# LED_BRD.net
KiCad netlist of a schematic drawn in EAGLE
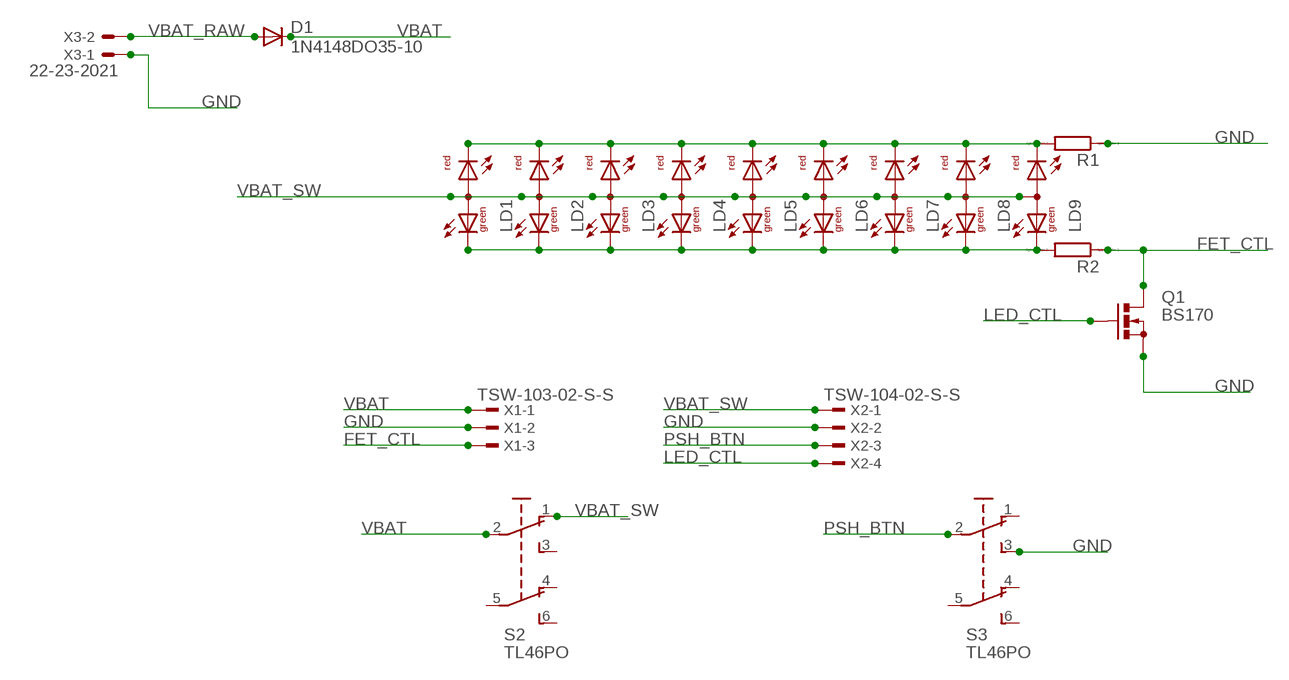
[diagram p0: schematic, sheet 1]

(export (version "E")
  (design (tool "Eeschema 10.0.6"))
  (components
    (comp (ref "D1")
      (value "1N4148DO35-10")
      (footprint "eagle-import:DO35-10")
      (libsource (lib "eagle-import") (part "1N4148DO35-10"))
    )
    (comp (ref "LD1")
      (value "DUOLED-RG-A")
      (footprint "eagle-import:DUOLED-A-5MM")
      (libsource (lib "eagle-import") (part "DUOLED-RG-A"))
    )
    (comp (ref "LD2")
      (value "DUOLED-RG-A")
      (footprint "eagle-import:DUOLED-A-5MM")
      (libsource (lib "eagle-import") (part "DUOLED-RG-A"))
    )
    (comp (ref "LD3")
      (value "DUOLED-RG-A")
      (footprint "eagle-import:DUOLED-A-5MM")
      (libsource (lib "eagle-import") (part "DUOLED-RG-A"))
    )
    (comp (ref "LD4")
      (value "DUOLED-RG-A")
      (footprint "eagle-import:DUOLED-A-5MM")
      (libsource (lib "eagle-import") (part "DUOLED-RG-A"))
    )
    (comp (ref "LD5")
      (value "DUOLED-RG-A")
      (footprint "eagle-import:DUOLED-A-5MM")
      (libsource (lib "eagle-import") (part "DUOLED-RG-A"))
    )
    (comp (ref "LD6")
      (value "DUOLED-RG-A")
      (footprint "eagle-import:DUOLED-A-5MM")
      (libsource (lib "eagle-import") (part "DUOLED-RG-A"))
    )
    (comp (ref "LD7")
      (value "DUOLED-RG-A")
      (footprint "eagle-import:DUOLED-A-5MM")
      (libsource (lib "eagle-import") (part "DUOLED-RG-A"))
    )
    (comp (ref "LD8")
      (value "DUOLED-RG-A")
      (footprint "eagle-import:DUOLED-A-5MM")
      (libsource (lib "eagle-import") (part "DUOLED-RG-A"))
    )
    (comp (ref "LD9")
      (value "DUOLED-RG-A")
      (footprint "eagle-import:DUOLED-A-5MM")
      (libsource (lib "eagle-import") (part "DUOLED-RG-A"))
    )
    (comp (ref "Q1")
      (value "BS170")
      (footprint "eagle-import:SOT54E")
      (libsource (lib "eagle-import") (part "BS170"))
    )
    (comp (ref "R1")
      (value "R0204/7")
      (footprint "eagle-import:0204_7")
      (libsource (lib "eagle-import") (part "R0204/7"))
    )
    (comp (ref "R2")
      (value "R0204/7")
      (footprint "eagle-import:0204_7")
      (libsource (lib "eagle-import") (part "R0204/7"))
    )
    (comp (ref "S2")
      (value "TL46PO")
      (footprint "eagle-import:TL4XPO")
      (libsource (lib "eagle-import") (part "TL46PO"))
    )
    (comp (ref "S3")
      (value "TL46PO")
      (footprint "eagle-import:TL4XPO")
      (libsource (lib "eagle-import") (part "TL46PO"))
    )
    (comp (ref "X1")
      (value "TSW-103-02-S-S")
      (footprint "eagle-import:TSW-103-02-S-S")
      (libsource (lib "eagle-import") (part "TSW-103-02-S-S"))
    )
    (comp (ref "X2")
      (value "TSW-104-02-S-S")
      (footprint "eagle-import:TSW-104-02-S-S")
      (libsource (lib "eagle-import") (part "TSW-104-02-S-S"))
    )
    (comp (ref "X3")
      (value "22-23-2021")
      (footprint "eagle-import:22-23-2021")
      (fields (field (name "MF") "MOLEX"))
      (libsource (lib "eagle-import") (part "22-23-2021"))
    )
  )
  (nets
    (net (code "1") (name "/FET_CTL") (class "Default")
      (node (ref "Q1") (pin "D") (pinfunction "D_D") (pintype "passive"))
      (node (ref "R2") (pin "1") (pinfunction "1_1") (pintype "passive"))
      (node (ref "X1") (pin "3") (pinfunction "1_3") (pintype "passive"))
    )
    (net (code "2") (name "/GND") (class "Default")
      (node (ref "Q1") (pin "S") (pinfunction "S_S") (pintype "passive"))
      (node (ref "R1") (pin "1") (pinfunction "1_1") (pintype "passive"))
      (node (ref "S3") (pin "3") (pinfunction "S_3") (pintype "passive"))
      (node (ref "X1") (pin "2") (pinfunction "1_2") (pintype "passive"))
      (node (ref "X2") (pin "2") (pinfunction "1_2") (pintype "passive"))
      (node (ref "X3") (pin "1") (pinfunction "S_1") (pintype "passive"))
    )
    (net (code "3") (name "/LED_CTL") (class "Default")
      (node (ref "Q1") (pin "G") (pinfunction "G_G") (pintype "passive"))
      (node (ref "X2") (pin "4") (pinfunction "1_4") (pintype "passive"))
    )
    (net (code "4") (name "/PSH_BTN") (class "Default")
      (node (ref "S3") (pin "2") (pinfunction "P_2") (pintype "passive"))
      (node (ref "X2") (pin "3") (pinfunction "1_3") (pintype "passive"))
    )
    (net (code "5") (name "/VBAT") (class "Default")
      (node (ref "D1") (pin "C") (pinfunction "C_C") (pintype "passive"))
      (node (ref "S2") (pin "2") (pinfunction "P_2") (pintype "passive"))
      (node (ref "X1") (pin "1") (pinfunction "1_1") (pintype "passive"))
    )
    (net (code "6") (name "/VBAT_RAW") (class "Default")
      (node (ref "D1") (pin "A") (pinfunction "A_A") (pintype "passive"))
      (node (ref "X3") (pin "2") (pinfunction "S_2") (pintype "passive"))
    )
    (net (code "7") (name "/VBAT_SW") (class "Default")
      (node (ref "LD1") (pin "A") (pinfunction "A_A") (pintype "passive"))
      (node (ref "LD2") (pin "A") (pinfunction "A_A") (pintype "passive"))
      (node (ref "LD3") (pin "A") (pinfunction "A_A") (pintype "passive"))
      (node (ref "LD4") (pin "A") (pinfunction "A_A") (pintype "passive"))
      (node (ref "LD5") (pin "A") (pinfunction "A_A") (pintype "passive"))
      (node (ref "LD6") (pin "A") (pinfunction "A_A") (pintype "passive"))
      (node (ref "LD7") (pin "A") (pinfunction "A_A") (pintype "passive"))
      (node (ref "LD8") (pin "A") (pinfunction "A_A") (pintype "passive"))
      (node (ref "LD9") (pin "A") (pinfunction "A_A") (pintype "passive"))
      (node (ref "S2") (pin "1") (pinfunction "O_1") (pintype "passive"))
      (node (ref "X2") (pin "1") (pinfunction "1_1") (pintype "passive"))
    )
    (net (code "8") (name "Net-(LD1-CG)") (class "Default")
      (node (ref "LD1") (pin "CX") (pinfunction "CG_CX") (pintype "passive"))
      (node (ref "LD2") (pin "CX") (pinfunction "CG_CX") (pintype "passive"))
      (node (ref "LD3") (pin "CX") (pinfunction "CG_CX") (pintype "passive"))
      (node (ref "LD4") (pin "CX") (pinfunction "CG_CX") (pintype "passive"))
      (node (ref "LD5") (pin "CX") (pinfunction "CG_CX") (pintype "passive"))
      (node (ref "LD6") (pin "CX") (pinfunction "CG_CX") (pintype "passive"))
      (node (ref "LD7") (pin "CX") (pinfunction "CG_CX") (pintype "passive"))
      (node (ref "LD8") (pin "CX") (pinfunction "CG_CX") (pintype "passive"))
      (node (ref "LD9") (pin "CX") (pinfunction "CG_CX") (pintype "passive"))
      (node (ref "R2") (pin "2") (pinfunction "2_2") (pintype "passive"))
    )
    (net (code "9") (name "Net-(LD1-PadCR)") (class "Default")
      (node (ref "LD1") (pin "CR") (pinfunction "CR_CR") (pintype "passive"))
      (node (ref "LD2") (pin "CR") (pinfunction "CR_CR") (pintype "passive"))
      (node (ref "LD3") (pin "CR") (pinfunction "CR_CR") (pintype "passive"))
      (node (ref "LD4") (pin "CR") (pinfunction "CR_CR") (pintype "passive"))
      (node (ref "LD5") (pin "CR") (pinfunction "CR_CR") (pintype "passive"))
      (node (ref "LD6") (pin "CR") (pinfunction "CR_CR") (pintype "passive"))
      (node (ref "LD7") (pin "CR") (pinfunction "CR_CR") (pintype "passive"))
      (node (ref "LD8") (pin "CR") (pinfunction "CR_CR") (pintype "passive"))
      (node (ref "LD9") (pin "CR") (pinfunction "CR_CR") (pintype "passive"))
      (node (ref "R1") (pin "2") (pinfunction "2_2") (pintype "passive"))
    )
    (net (code "10") (name "unconnected-(S2-O1-Pad4)") (class "Default")
      (node (ref "S2") (pin "4") (pinfunction "O1_4") (pintype "passive"))
    )
    (net (code "11") (name "unconnected-(S2-P1-Pad5)") (class "Default")
      (node (ref "S2") (pin "5") (pinfunction "P1_5") (pintype "passive"))
    )
    (net (code "12") (name "unconnected-(S2-S-Pad3)") (class "Default")
      (node (ref "S2") (pin "3") (pinfunction "S_3") (pintype "passive"))
    )
    (net (code "13") (name "unconnected-(S2-S1-Pad6)") (class "Default")
      (node (ref "S2") (pin "6") (pinfunction "S1_6") (pintype "passive"))
    )
    (net (code "14") (name "unconnected-(S3-O-Pad1)") (class "Default")
      (node (ref "S3") (pin "1") (pinfunction "O_1") (pintype "passive"))
    )
    (net (code "15") (name "unconnected-(S3-O1-Pad4)") (class "Default")
      (node (ref "S3") (pin "4") (pinfunction "O1_4") (pintype "passive"))
    )
    (net (code "16") (name "unconnected-(S3-P1-Pad5)") (class "Default")
      (node (ref "S3") (pin "5") (pinfunction "P1_5") (pintype "passive"))
    )
    (net (code "17") (name "unconnected-(S3-S1-Pad6)") (class "Default")
      (node (ref "S3") (pin "6") (pinfunction "S1_6") (pintype "passive"))
    )
  )
)
